# 2_stepper_board.net
KiCad netlist of a schematic drawn in EAGLE
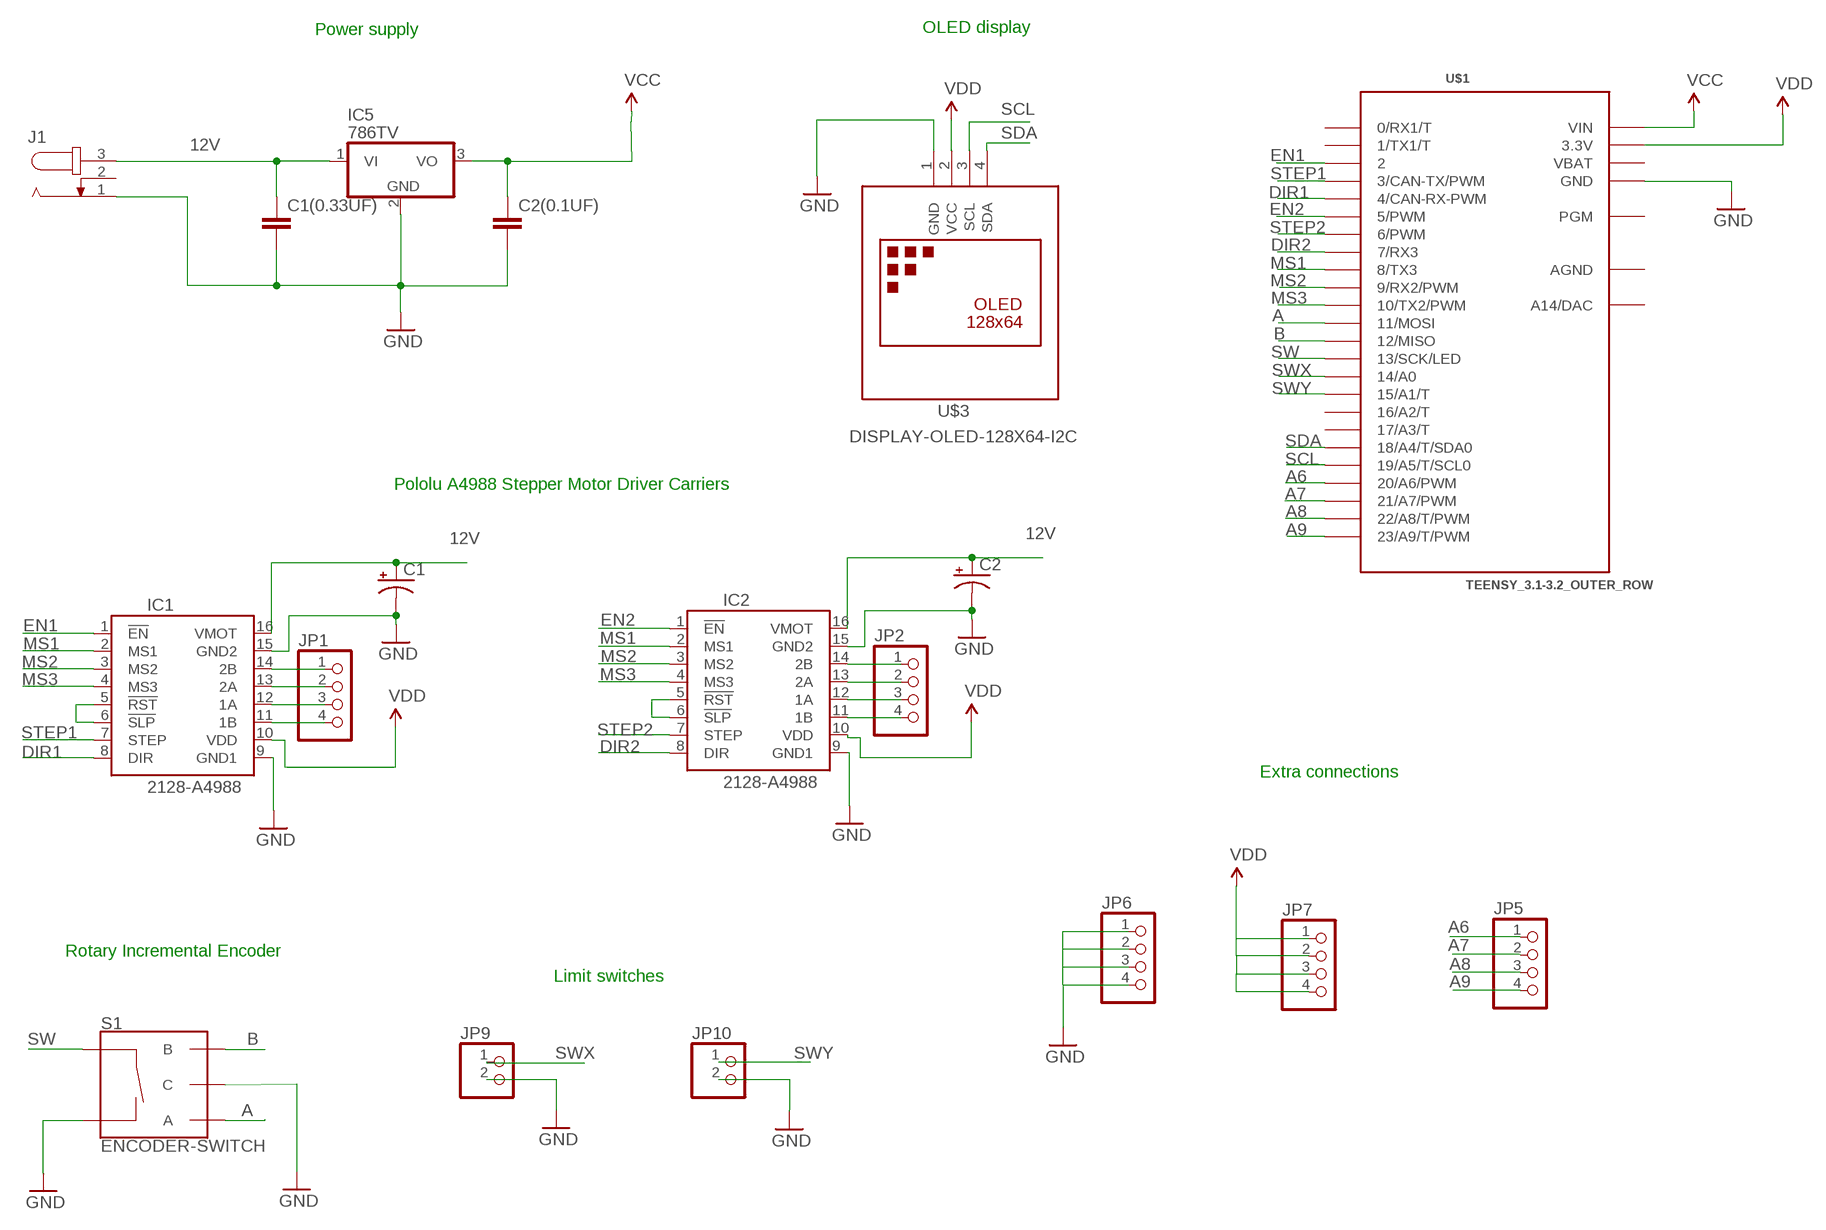
[diagram p0: schematic, sheet 1]

(export (version "E")
  (design (tool "Eeschema 10.0.6"))
  (components
    (comp (ref "C1")
      (value "CPOL-USE5-5")
      (footprint "eagle-import:E5-5")
      (libsource (lib "eagle-import") (part "CPOL-USE5-5"))
    )
    (comp (ref "C1(0.33UF)")
      (value "C2.5/4")
      (footprint "eagle-import:C2.5-4")
      (libsource (lib "eagle-import") (part "C2.5/4"))
    )
    (comp (ref "C2")
      (value "CPOL-USE5-5")
      (footprint "eagle-import:E5-5")
      (libsource (lib "eagle-import") (part "CPOL-USE5-5"))
    )
    (comp (ref "C2(0.1UF)")
      (value "C2.5/2")
      (footprint "eagle-import:C2.5-2")
      (libsource (lib "eagle-import") (part "C2.5/2"))
    )
    (comp (ref "IC1")
      (value "2128-A4988")
      (footprint "eagle-import:A4988")
      (libsource (lib "eagle-import") (part "2128-A4988"))
    )
    (comp (ref "IC2")
      (value "2128-A4988")
      (footprint "eagle-import:A4988")
      (libsource (lib "eagle-import") (part "2128-A4988"))
    )
    (comp (ref "IC5")
      (value "786TV")
      (footprint "eagle-import:TO220V")
      (libsource (lib "eagle-import") (part "78TV6"))
    )
    (comp (ref "J1")
      (value "JACK-PLUG0")
      (footprint "eagle-import:SPC4077")
      (libsource (lib "eagle-import") (part "JACK-PLUG0"))
    )
    (comp (ref "JP1")
      (value "PINHD-1X4")
      (footprint "eagle-import:1X04")
      (libsource (lib "eagle-import") (part "PINHD-1X4"))
    )
    (comp (ref "JP2")
      (value "PINHD-1X4")
      (footprint "eagle-import:1X04")
      (libsource (lib "eagle-import") (part "PINHD-1X4"))
    )
    (comp (ref "JP5")
      (value "PINHD-1X4")
      (footprint "eagle-import:1X04")
      (libsource (lib "eagle-import") (part "PINHD-1X4"))
    )
    (comp (ref "JP6")
      (value "PINHD-1X4")
      (footprint "eagle-import:1X04")
      (libsource (lib "eagle-import") (part "PINHD-1X4"))
    )
    (comp (ref "JP7")
      (value "PINHD-1X4")
      (footprint "eagle-import:1X04")
      (libsource (lib "eagle-import") (part "PINHD-1X4"))
    )
    (comp (ref "JP9")
      (value "PINHD-1X2")
      (footprint "eagle-import:1X02")
      (libsource (lib "eagle-import") (part "PINHD-1X2"))
    )
    (comp (ref "JP10")
      (value "PINHD-1X2")
      (footprint "eagle-import:1X02")
      (libsource (lib "eagle-import") (part "PINHD-1X2"))
    )
    (comp (ref "S1")
      (value "ENCODER-SWITCH")
      (footprint "eagle-import:ROTARY_ENC_PLAIN")
      (libsource (lib "eagle-import") (part "ENCODER-SWITCH"))
    )
    (comp (ref "U$1")
      (value "TEENSY_3.1-3.2_OUTER_ROW")
      (footprint "eagle-import:TEENSY_3.0-3.2&LC_OUTER_ROW")
      (libsource (lib "eagle-import") (part "TEENSY_3.1-3.2_OUTER_ROW"))
    )
    (comp (ref "U$3")
      (value "DISPLAY-OLED-128X64-I2C")
      (footprint "eagle-import:DISPLAY-OLED-128X64-I2C")
      (libsource (lib "eagle-import") (part "DISPLAY-OLED-128X64-I2C"))
    )
  )
  (nets
    (net (code "1") (name "/12V") (class "Default")
      (node (ref "C1") (pin "+") (pinfunction "+_+") (pintype "passive"))
      (node (ref "C1(0.33UF)") (pin "1") (pinfunction "1_1") (pintype "passive"))
      (node (ref "C2") (pin "+") (pinfunction "+_+") (pintype "passive"))
      (node (ref "IC1") (pin "16") (pinfunction "VMOT_16") (pintype "power_in"))
      (node (ref "IC2") (pin "16") (pinfunction "VMOT_16") (pintype "power_in"))
      (node (ref "IC5") (pin "1") (pinfunction "VI_1") (pintype "input"))
      (node (ref "J1") (pin "3") (pinfunction "3_3") (pintype "passive"))
    )
    (net (code "2") (name "/A") (class "Default")
      (node (ref "S1") (pin "A") (pinfunction "A_A") (pintype "bidirectional"))
      (node (ref "U$1") (pin "11") (pinfunction "11/MOSI_11") (pintype "bidirectional"))
    )
    (net (code "3") (name "/A6") (class "Default")
      (node (ref "JP5") (pin "1") (pinfunction "1_1") (pintype "passive"))
      (node (ref "U$1") (pin "20/A6") (pinfunction "20/A6/PWM_20/A6") (pintype "bidirectional"))
    )
    (net (code "4") (name "/A7") (class "Default")
      (node (ref "JP5") (pin "2") (pinfunction "2_2") (pintype "passive"))
      (node (ref "U$1") (pin "21/A7") (pinfunction "21/A7/PWM_21/A7") (pintype "bidirectional"))
    )
    (net (code "5") (name "/A8") (class "Default")
      (node (ref "JP5") (pin "3") (pinfunction "3_3") (pintype "passive"))
      (node (ref "U$1") (pin "22/A8") (pinfunction "22/A8/T/PWM_22/A8") (pintype "bidirectional"))
    )
    (net (code "6") (name "/A9") (class "Default")
      (node (ref "JP5") (pin "4") (pinfunction "4_4") (pintype "passive"))
      (node (ref "U$1") (pin "23/A9") (pinfunction "23/A9/T/PWM_23/A9") (pintype "bidirectional"))
    )
    (net (code "7") (name "/AGND") (class "Default")
      (node (ref "U$1") (pin "AGND") (pinfunction "AGND_AGND") (pintype "power_in"))
    )
    (net (code "8") (name "/B") (class "Default")
      (node (ref "S1") (pin "B") (pinfunction "B_B") (pintype "bidirectional"))
      (node (ref "U$1") (pin "12") (pinfunction "12/MISO_12") (pintype "bidirectional"))
    )
    (net (code "9") (name "/DIR1") (class "Default")
      (node (ref "IC1") (pin "8") (pinfunction "DIR_8") (pintype "input"))
      (node (ref "U$1") (pin "4") (pinfunction "4/CAN-RX-PWM_4") (pintype "bidirectional"))
    )
    (net (code "10") (name "/DIR2") (class "Default")
      (node (ref "IC2") (pin "8") (pinfunction "DIR_8") (pintype "input"))
      (node (ref "U$1") (pin "7") (pinfunction "7/RX3_7") (pintype "bidirectional"))
    )
    (net (code "11") (name "/EN1") (class "Default")
      (node (ref "IC1") (pin "1") (pinfunction "~{EN}_1") (pintype "passive"))
      (node (ref "U$1") (pin "2") (pinfunction "2_2") (pintype "bidirectional"))
    )
    (net (code "12") (name "/EN2") (class "Default")
      (node (ref "IC2") (pin "1") (pinfunction "~{EN}_1") (pintype "passive"))
      (node (ref "U$1") (pin "5") (pinfunction "5/PWM_5") (pintype "bidirectional"))
    )
    (net (code "13") (name "/MS1") (class "Default")
      (node (ref "IC1") (pin "2") (pinfunction "MS1_2") (pintype "passive"))
      (node (ref "IC2") (pin "2") (pinfunction "MS1_2") (pintype "passive"))
      (node (ref "U$1") (pin "8") (pinfunction "8/TX3_8") (pintype "bidirectional"))
    )
    (net (code "14") (name "/MS2") (class "Default")
      (node (ref "IC1") (pin "3") (pinfunction "MS2_3") (pintype "passive"))
      (node (ref "IC2") (pin "3") (pinfunction "MS2_3") (pintype "passive"))
      (node (ref "U$1") (pin "9") (pinfunction "9/RX2/PWM_9") (pintype "bidirectional"))
    )
    (net (code "15") (name "/MS3") (class "Default")
      (node (ref "IC1") (pin "4") (pinfunction "MS3_4") (pintype "passive"))
      (node (ref "IC2") (pin "4") (pinfunction "MS3_4") (pintype "passive"))
      (node (ref "U$1") (pin "10") (pinfunction "10/TX2/PWM_10") (pintype "bidirectional"))
    )
    (net (code "16") (name "/SCL") (class "Default")
      (node (ref "U$1") (pin "19/A5") (pinfunction "19/A5/T/SCL0_19/A5") (pintype "bidirectional"))
      (node (ref "U$3") (pin "3") (pinfunction "SCL_3") (pintype "bidirectional"))
    )
    (net (code "17") (name "/SDA") (class "Default")
      (node (ref "U$1") (pin "18/A4") (pinfunction "18/A4/T/SDA0_18/A4") (pintype "bidirectional"))
      (node (ref "U$3") (pin "4") (pinfunction "SDA_4") (pintype "bidirectional"))
    )
    (net (code "18") (name "/STEP1") (class "Default")
      (node (ref "IC1") (pin "7") (pinfunction "STEP_7") (pintype "input"))
      (node (ref "U$1") (pin "3") (pinfunction "3/CAN-TX/PWM_3") (pintype "bidirectional"))
    )
    (net (code "19") (name "/STEP2") (class "Default")
      (node (ref "IC2") (pin "7") (pinfunction "STEP_7") (pintype "input"))
      (node (ref "U$1") (pin "6") (pinfunction "6/PWM_6") (pintype "bidirectional"))
    )
    (net (code "20") (name "/SW") (class "Default")
      (node (ref "S1") (pin "SW+") (pinfunction "SW+_SW+") (pintype "bidirectional"))
      (node (ref "U$1") (pin "13") (pinfunction "13/SCK/LED_13") (pintype "bidirectional"))
    )
    (net (code "21") (name "/SWX") (class "Default")
      (node (ref "JP9") (pin "1") (pinfunction "1_1") (pintype "passive"))
      (node (ref "U$1") (pin "14/A0") (pinfunction "14/A0_14/A0") (pintype "bidirectional"))
    )
    (net (code "22") (name "/SWY") (class "Default")
      (node (ref "JP10") (pin "1") (pinfunction "1_1") (pintype "passive"))
      (node (ref "U$1") (pin "15/A1") (pinfunction "15/A1/T_15/A1") (pintype "bidirectional"))
    )
    (net (code "23") (name "/VBAT") (class "Default")
      (node (ref "U$1") (pin "VBAT") (pinfunction "VBAT_VBAT") (pintype "power_in"))
    )
    (net (code "24") (name "GND") (class "Default")
      (node (ref "C1") (pin "-") (pinfunction "-_-") (pintype "passive"))
      (node (ref "C1(0.33UF)") (pin "2") (pinfunction "2_2") (pintype "passive"))
      (node (ref "C2") (pin "-") (pinfunction "-_-") (pintype "passive"))
      (node (ref "C2(0.1UF)") (pin "2") (pinfunction "2_2") (pintype "passive"))
      (node (ref "IC1") (pin "15") (pinfunction "GND2_15") (pintype "power_in"))
      (node (ref "IC1") (pin "9") (pinfunction "GND1_9") (pintype "power_in"))
      (node (ref "IC2") (pin "15") (pinfunction "GND2_15") (pintype "power_in"))
      (node (ref "IC2") (pin "9") (pinfunction "GND1_9") (pintype "power_in"))
      (node (ref "IC5") (pin "2") (pinfunction "GND_2") (pintype "passive"))
      (node (ref "J1") (pin "1") (pinfunction "1_1") (pintype "passive"))
      (node (ref "JP10") (pin "2") (pinfunction "2_2") (pintype "passive"))
      (node (ref "JP6") (pin "1") (pinfunction "1_1") (pintype "passive"))
      (node (ref "JP6") (pin "2") (pinfunction "2_2") (pintype "passive"))
      (node (ref "JP6") (pin "3") (pinfunction "3_3") (pintype "passive"))
      (node (ref "JP6") (pin "4") (pinfunction "4_4") (pintype "passive"))
      (node (ref "JP9") (pin "2") (pinfunction "2_2") (pintype "passive"))
      (node (ref "S1") (pin "C") (pinfunction "C_C") (pintype "bidirectional"))
      (node (ref "S1") (pin "SW-") (pinfunction "SW-_SW-") (pintype "bidirectional"))
      (node (ref "U$1") (pin "GND") (pinfunction "GND_GND") (pintype "power_in"))
      (node (ref "U$1") (pin "GND1") (pinfunction "GND_GND1") (pintype "power_in"))
      (node (ref "U$3") (pin "1") (pinfunction "GND_1") (pintype "power_in"))
    )
    (net (code "25") (name "Net-(IC1-1A)") (class "Default")
      (node (ref "IC1") (pin "12") (pinfunction "1A_12") (pintype "output"))
      (node (ref "JP1") (pin "3") (pinfunction "3_3") (pintype "passive"))
    )
    (net (code "26") (name "Net-(IC1-1B)") (class "Default")
      (node (ref "IC1") (pin "11") (pinfunction "1B_11") (pintype "output"))
      (node (ref "JP1") (pin "4") (pinfunction "4_4") (pintype "passive"))
    )
    (net (code "27") (name "Net-(IC1-2A)") (class "Default")
      (node (ref "IC1") (pin "13") (pinfunction "2A_13") (pintype "output"))
      (node (ref "JP1") (pin "2") (pinfunction "2_2") (pintype "passive"))
    )
    (net (code "28") (name "Net-(IC1-2B)") (class "Default")
      (node (ref "IC1") (pin "14") (pinfunction "2B_14") (pintype "output"))
      (node (ref "JP1") (pin "1") (pinfunction "1_1") (pintype "passive"))
    )
    (net (code "29") (name "Net-(IC1-~{RST})") (class "Default")
      (node (ref "IC1") (pin "5") (pinfunction "~{RST}_5") (pintype "passive"))
      (node (ref "IC1") (pin "6") (pinfunction "~{SLP}_6") (pintype "passive"))
    )
    (net (code "30") (name "Net-(IC2-1A)") (class "Default")
      (node (ref "IC2") (pin "12") (pinfunction "1A_12") (pintype "output"))
      (node (ref "JP2") (pin "3") (pinfunction "3_3") (pintype "passive"))
    )
    (net (code "31") (name "Net-(IC2-1B)") (class "Default")
      (node (ref "IC2") (pin "11") (pinfunction "1B_11") (pintype "output"))
      (node (ref "JP2") (pin "4") (pinfunction "4_4") (pintype "passive"))
    )
    (net (code "32") (name "Net-(IC2-2A)") (class "Default")
      (node (ref "IC2") (pin "13") (pinfunction "2A_13") (pintype "output"))
      (node (ref "JP2") (pin "2") (pinfunction "2_2") (pintype "passive"))
    )
    (net (code "33") (name "Net-(IC2-2B)") (class "Default")
      (node (ref "IC2") (pin "14") (pinfunction "2B_14") (pintype "output"))
      (node (ref "JP2") (pin "1") (pinfunction "1_1") (pintype "passive"))
    )
    (net (code "34") (name "Net-(IC2-~{RST})") (class "Default")
      (node (ref "IC2") (pin "5") (pinfunction "~{RST}_5") (pintype "passive"))
      (node (ref "IC2") (pin "6") (pinfunction "~{SLP}_6") (pintype "passive"))
    )
    (net (code "35") (name "VCC") (class "Default")
      (node (ref "C2(0.1UF)") (pin "1") (pinfunction "1_1") (pintype "passive"))
      (node (ref "IC5") (pin "3") (pinfunction "VO_3") (pintype "passive"))
      (node (ref "U$1") (pin "VIN") (pinfunction "VIN_VIN") (pintype "power_in"))
    )
    (net (code "36") (name "VDD") (class "Default")
      (node (ref "IC1") (pin "10") (pinfunction "VDD_10") (pintype "power_in"))
      (node (ref "IC2") (pin "10") (pinfunction "VDD_10") (pintype "power_in"))
      (node (ref "JP7") (pin "1") (pinfunction "1_1") (pintype "passive"))
      (node (ref "JP7") (pin "2") (pinfunction "2_2") (pintype "passive"))
      (node (ref "JP7") (pin "3") (pinfunction "3_3") (pintype "passive"))
      (node (ref "JP7") (pin "4") (pinfunction "4_4") (pintype "passive"))
      (node (ref "U$1") (pin "3.3V") (pinfunction "3.3V_3.3V") (pintype "power_in"))
      (node (ref "U$1") (pin "3.3V1") (pinfunction "3.3V_3.3V1") (pintype "power_in"))
      (node (ref "U$3") (pin "2") (pinfunction "VCC_2") (pintype "power_in"))
    )
    (net (code "37") (name "unconnected-(J1-Pad2)") (class "Default")
      (node (ref "J1") (pin "2") (pinfunction "2_2") (pintype "passive"))
    )
    (net (code "38") (name "unconnected-(U$1-0{slash}RX1{slash}T-Pad0)") (class "Default")
      (node (ref "U$1") (pin "0") (pinfunction "0/RX1/T_0") (pintype "bidirectional"))
    )
    (net (code "39") (name "unconnected-(U$1-1{slash}TX1{slash}T-Pad1)") (class "Default")
      (node (ref "U$1") (pin "1") (pinfunction "1/TX1/T_1") (pintype "bidirectional"))
    )
    (net (code "40") (name "unconnected-(U$1-16{slash}A2{slash}T-Pad16{slash}A2)") (class "Default")
      (node (ref "U$1") (pin "16/A2") (pinfunction "16/A2/T_16/A2") (pintype "bidirectional"))
    )
    (net (code "41") (name "unconnected-(U$1-17{slash}A3{slash}T-Pad17{slash}A3)") (class "Default")
      (node (ref "U$1") (pin "17/A3") (pinfunction "17/A3/T_17/A3") (pintype "bidirectional"))
    )
    (net (code "42") (name "unconnected-(U$1-A14{slash}DAC-PadRESET{slash}DAC)") (class "Default")
      (node (ref "U$1") (pin "RESET/DAC") (pinfunction "A14/DAC_RESET/DAC") (pintype "bidirectional"))
    )
    (net (code "43") (name "unconnected-(U$1-PadPGM)") (class "Default")
      (node (ref "U$1") (pin "PGM") (pinfunction "PGM_PGM") (pintype "bidirectional"))
    )
  )
)
